# GSM_Power_On-Off_Switch_IC.net
KiCad netlist of a schematic drawn in Altium Designer
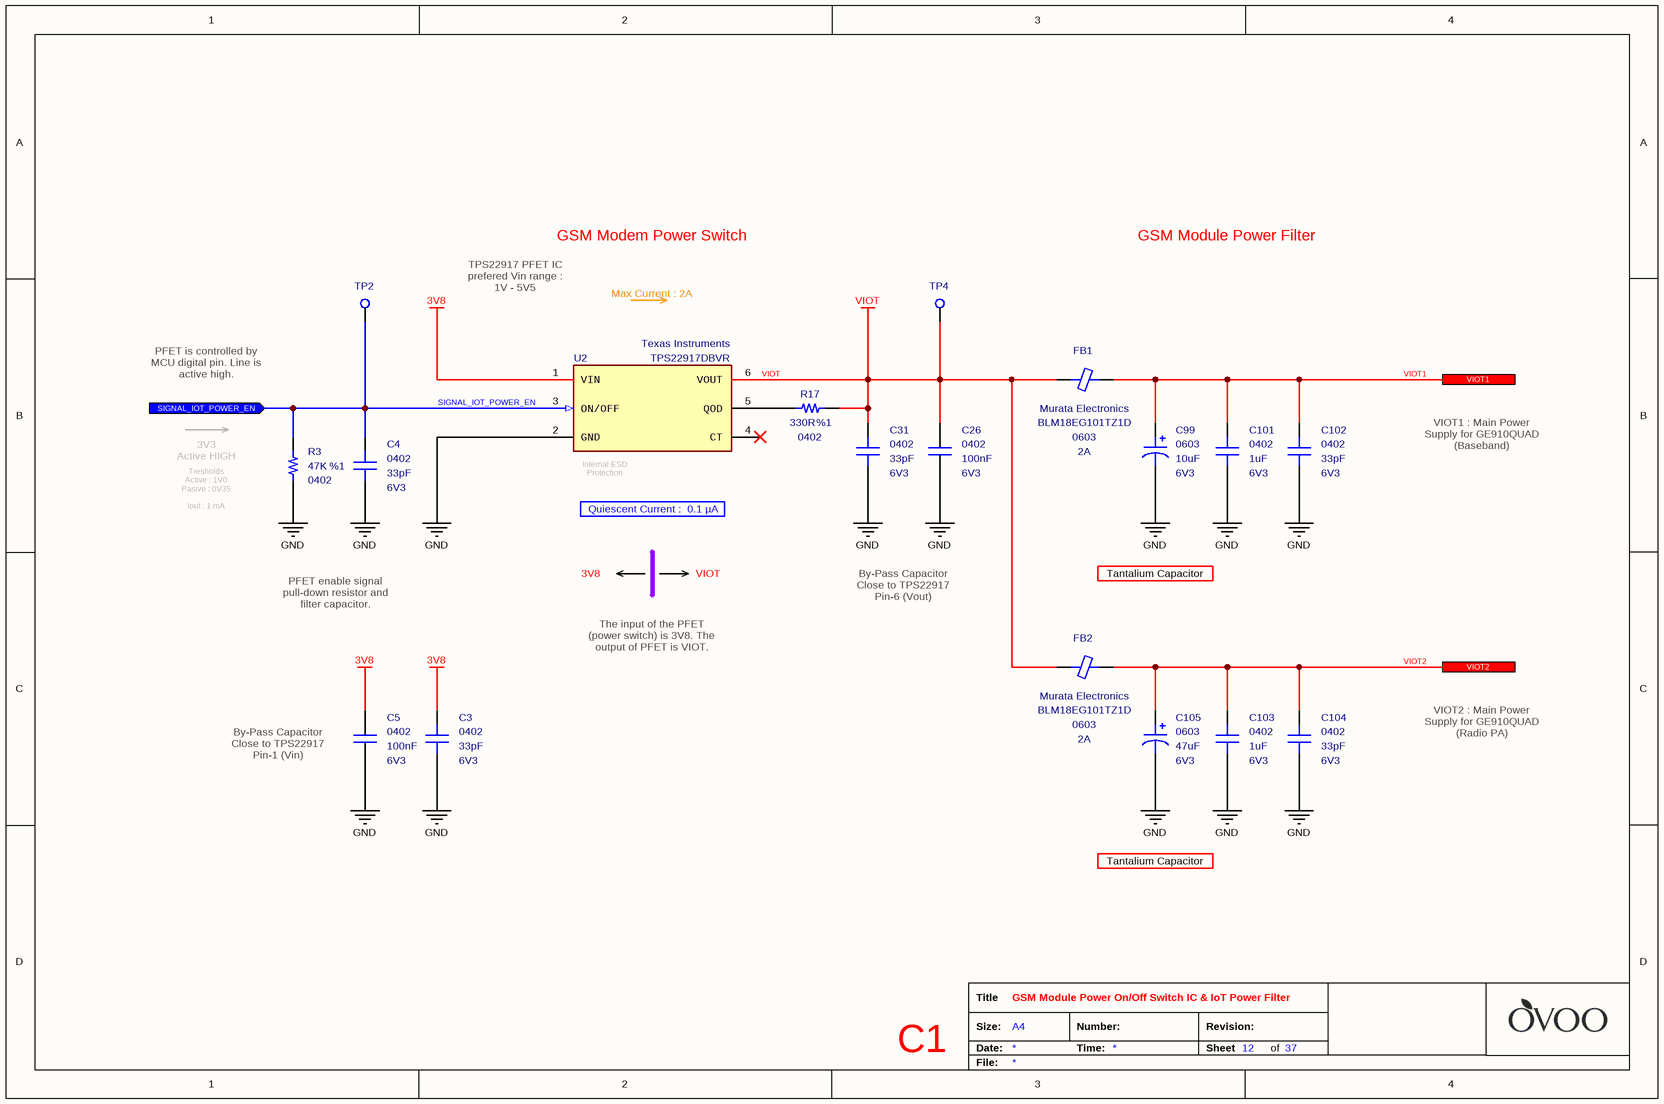
[diagram p0: GSM Power On-Off Switch IC.SchDoc]

(export (version "E")
  (design (tool "Eeschema 10.0.6"))
  (components
    (comp (ref "C3")
      (value "33pF")
      (footprint "CAPACITOR_0402")
      (description "Capacitor - 33pF [0402] (Ceramic)")
      (fields
        (field (name "MANUFACTURER_PART_NUMBER") "C0402C330J9RACAUTO")
        (field (name "MOUSER_PART_NUMBER") "80-C0402C330J9RAUTO")
        (field (name "CASE") "0402")
        (field (name "VOLTAGE") "6V3")
      )
      (libsource (lib "Ovoo_Schematic") (part "Capacitor - 33pF [0402-6V3]"))
    )
    (comp (ref "C4")
      (value "33pF")
      (footprint "CAPACITOR_0402")
      (description "Capacitor - 33pF [0402] (Ceramic)")
      (fields
        (field (name "MANUFACTURER_PART_NUMBER") "C0402C330J9RACAUTO")
        (field (name "MOUSER_PART_NUMBER") "80-C0402C330J9RAUTO")
        (field (name "CASE") "0402")
        (field (name "VOLTAGE") "6V3")
      )
      (libsource (lib "Ovoo_Schematic") (part "Capacitor - 33pF [0402-6V3]"))
    )
    (comp (ref "C5")
      (value "100nF")
      (footprint "CAPACITOR_0402")
      (description "Capacitor - 100nF [0402-6V3] (Ceramic)")
      (fields
        (field (name "MANUFACTURER_PART_NUMBER") "04026D104KAT4A")
        (field (name "MOUSER_PART_NUMBER") "581-04026D104KAT4A")
        (field (name "CASE") "0402")
        (field (name "VOLTAGE") "6V3")
      )
      (libsource (lib "Ovoo_Schematic") (part "Capacitor - 100nF [0402-6V3]"))
    )
    (comp (ref "C26")
      (value "100nF")
      (footprint "CAPACITOR_0402")
      (description "Capacitor - 100nF [0402-6V3] (Ceramic)")
      (fields
        (field (name "MANUFACTURER_PART_NUMBER") "04026D104KAT4A")
        (field (name "MOUSER_PART_NUMBER") "581-04026D104KAT4A")
        (field (name "CASE") "0402")
        (field (name "VOLTAGE") "6V3")
      )
      (libsource (lib "Ovoo_Schematic") (part "Capacitor - 100nF [0402-6V3]"))
    )
    (comp (ref "C31")
      (value "33pF")
      (footprint "CAPACITOR_0402")
      (description "Capacitor - 33pF [0402] (Ceramic)")
      (fields
        (field (name "MANUFACTURER_PART_NUMBER") "C0402C330J9RACAUTO")
        (field (name "MOUSER_PART_NUMBER") "80-C0402C330J9RAUTO")
        (field (name "CASE") "0402")
        (field (name "VOLTAGE") "6V3")
      )
      (libsource (lib "Ovoo_Schematic") (part "Capacitor - 33pF [0402-6V3]"))
    )
    (comp (ref "C99")
      (value "10uF")
      (footprint "CAPACITOR_0603 - TANTALUM")
      (description "Capacitor - 10uF [0603] (Tantalium)")
      (fields
        (field (name "MANUFACTURER_PART_NUMBER") "F380J106MMAAH3")
        (field (name "MOUSER_PART_NUMBER") "581-F380J106MMAAH3")
        (field (name "CASE") "0603")
        (field (name "VOLTAGE") "6V3")
      )
      (libsource (lib "Ovoo_Schematic") (part "Capacitor - 10uF [0603-6V3] (Tantalium)"))
    )
    (comp (ref "C101")
      (value "1uF")
      (footprint "CAPACITOR_0402")
      (description "Capacitor - 1uF [0402] (Ceramic)")
      (fields
        (field (name "MANUFACTURER_PART_NUMBER") "GRM153R60J105ME95D")
        (field (name "MOUSER_PART_NUMBER") "81-GRM153R60J105ME5D")
        (field (name "CASE") "0402")
        (field (name "VOLTAGE") "6V3")
      )
      (libsource (lib "Ovoo_Schematic") (part "Capacitor - 1uF [0402-6V3)"))
    )
    (comp (ref "C102")
      (value "33pF")
      (footprint "CAPACITOR_0402")
      (description "Capacitor - 33pF [0402] (Ceramic)")
      (fields
        (field (name "MANUFACTURER_PART_NUMBER") "C0402C330J9RACAUTO")
        (field (name "MOUSER_PART_NUMBER") "80-C0402C330J9RAUTO")
        (field (name "CASE") "0402")
        (field (name "VOLTAGE") "6V3")
      )
      (libsource (lib "Ovoo_Schematic") (part "Capacitor - 33pF [0402-6V3]"))
    )
    (comp (ref "C103")
      (value "1uF")
      (footprint "CAPACITOR_0402")
      (description "Capacitor - 1uF [0402] (Ceramic)")
      (fields
        (field (name "MANUFACTURER_PART_NUMBER") "GRM153R60J105ME95D")
        (field (name "MOUSER_PART_NUMBER") "81-GRM153R60J105ME5D")
        (field (name "CASE") "0402")
        (field (name "VOLTAGE") "6V3")
      )
      (libsource (lib "Ovoo_Schematic") (part "Capacitor - 1uF [0402-6V3)"))
    )
    (comp (ref "C104")
      (value "33pF")
      (footprint "CAPACITOR_0402")
      (description "Capacitor - 33pF [0402] (Ceramic)")
      (fields
        (field (name "MANUFACTURER_PART_NUMBER") "C0402C330J9RACAUTO")
        (field (name "MOUSER_PART_NUMBER") "80-C0402C330J9RAUTO")
        (field (name "CASE") "0402")
        (field (name "VOLTAGE") "6V3")
      )
      (libsource (lib "Ovoo_Schematic") (part "Capacitor - 33pF [0402-6V3]"))
    )
    (comp (ref "C105")
      (value "47uF")
      (footprint "CAPACITOR_0603 - TANTALUM")
      (description "Capacitor - 47uF [0603] (Tantalium)")
      (fields
        (field (name "MANUFACTURER_PART_NUMBER") "F380J476MMAAXEH3")
        (field (name "MOUSER_PART_NUMBER") "581-F380J476MMAAXEH3")
        (field (name "CASE") "0603")
        (field (name "VOLTAGE") "6V3")
      )
      (libsource (lib "Ovoo_Schematic") (part "Capacitor - 47u [0603-6V3] (Tantalium)"))
    )
    (comp (ref "FB1")
      (value "BLM18EG101TZ1D")
      (footprint "INDUCATOR_0603")
      (description "Ferrite Beads 0603 100ohms 2000mA Auto Infotainment")
      (fields
        (field (name "MOUSER_PART_NUMBER") "81-BLM18EG101TZ1D")
        (field (name "TOLERANCE") "25%")
        (field (name "MANUFACTURER_NAME") "Murata Electronics")
        (field (name "CASE") "0603")
        (field (name "MAXIMUM DC CURRENT") "2A")
      )
      (libsource (lib "Ovoo_Schematic") (part "Ferrite Bead - 2A [0603]"))
    )
    (comp (ref "FB2")
      (value "BLM18EG101TZ1D")
      (footprint "INDUCATOR_0603")
      (description "Ferrite Beads 0603 100ohms 2000mA Auto Infotainment")
      (fields
        (field (name "MOUSER_PART_NUMBER") "81-BLM18EG101TZ1D")
        (field (name "TOLERANCE") "25%")
        (field (name "MANUFACTURER_NAME") "Murata Electronics")
        (field (name "CASE") "0603")
        (field (name "MAXIMUM DC CURRENT") "2A")
      )
      (libsource (lib "Ovoo_Schematic") (part "Ferrite Bead - 2A [0603]"))
    )
    (comp (ref "R3")
      (value "47K")
      (footprint "RESISTOR_0402")
      (description "Thick Film Resistors - SMD 1/16 W 47 Kohms 1%")
      (fields
        (field (name "MANUFACTURER_PART_NUMBER") "CRCW040247K0FKED")
        (field (name "MOUSER_PART_NUMBER") "71-CRCW0402-47K-E3")
        (field (name "TOLERANCE") "%1")
        (field (name "CASE") "0402")
      )
      (libsource (lib "Ovoo_Schematic") (part "Resistor - 47K"))
    )
    (comp (ref "R17")
      (value "330R")
      (footprint "RESISTOR_0402")
      (description "Thick Film Resistors - SMD 1/16 W 330 Ohm 1%")
      (fields
        (field (name "MANUFACTURER_PART_NUMBER") "CRCW0402330RFKED")
        (field (name "MOUSER_PART_NUMBER") "71-CRCW0402-330-E3")
        (field (name "TOLERANCE") "%1")
        (field (name "CASE") "0402")
      )
      (libsource (lib "Ovoo_Schematic") (part "Resistor - 330R"))
    )
    (comp (ref "TP2")
      (value "PCB - Test Point")
      (footprint "Test_Pad - Hole")
      (description "Test Point")
      (libsource (lib "Ovoo_Schematic") (part "PCB - Test Point"))
    )
    (comp (ref "TP4")
      (value "PCB - Test Point")
      (footprint "Test_Pad - Hole")
      (description "Test Point")
      (libsource (lib "Ovoo_Schematic") (part "PCB - Test Point"))
    )
    (comp (ref "U2")
      (value "Power Switch")
      (footprint "SOT-23-6")
      (description "Power Switch MosFet")
      (fields
        (field (name "MOUSER_PART_NUMBER") "595-TPS22917DBVR")
        (field (name "MANUFACTURER_PART_NUMBER") "TPS22917DBVR")
        (field (name "MANUFACTURER_NAME") "Texas Instruments")
      )
      (libsource (lib "Ovoo_Schematic") (part "IC - TPS22917DBVR"))
    )
  )
  (nets
    (net (code "1") (name "/SIGNAL_IOT_POWER_EN") (class "Default")
      (node (ref "C4") (pin "2") (pinfunction "2_2") (pintype "passive"))
      (node (ref "R3") (pin "2") (pinfunction "2_2") (pintype "passive"))
      (node (ref "TP2") (pin "1") (pinfunction "1_1") (pintype "passive"))
      (node (ref "U2") (pin "3") (pinfunction "ON/OFF_3") (pintype "input"))
    )
    (net (code "2") (name "/VIOT1") (class "Default")
      (node (ref "C101") (pin "2") (pinfunction "2_2") (pintype "passive"))
      (node (ref "C102") (pin "2") (pinfunction "2_2") (pintype "passive"))
      (node (ref "C99") (pin "1") (pinfunction "1_1") (pintype "passive"))
      (node (ref "FB1") (pin "2") (pinfunction "2_2") (pintype "passive"))
    )
    (net (code "3") (name "/VIOT2") (class "Default")
      (node (ref "C103") (pin "2") (pinfunction "2_2") (pintype "passive"))
      (node (ref "C104") (pin "2") (pinfunction "2_2") (pintype "passive"))
      (node (ref "C105") (pin "1") (pinfunction "1_1") (pintype "passive"))
      (node (ref "FB2") (pin "2") (pinfunction "2_2") (pintype "passive"))
    )
    (net (code "4") (name "3V8") (class "Default")
      (node (ref "C3") (pin "2") (pinfunction "2_2") (pintype "passive"))
      (node (ref "C5") (pin "1") (pinfunction "1_1") (pintype "passive"))
      (node (ref "U2") (pin "1") (pinfunction "VIN_1") (pintype "power_in"))
    )
    (net (code "5") (name "GND") (class "Default")
      (node (ref "C101") (pin "1") (pinfunction "1_1") (pintype "passive"))
      (node (ref "C102") (pin "1") (pinfunction "1_1") (pintype "passive"))
      (node (ref "C103") (pin "1") (pinfunction "1_1") (pintype "passive"))
      (node (ref "C104") (pin "1") (pinfunction "1_1") (pintype "passive"))
      (node (ref "C105") (pin "2") (pinfunction "2_2") (pintype "passive"))
      (node (ref "C26") (pin "2") (pinfunction "2_2") (pintype "passive"))
      (node (ref "C3") (pin "1") (pinfunction "1_1") (pintype "passive"))
      (node (ref "C31") (pin "1") (pinfunction "1_1") (pintype "passive"))
      (node (ref "C4") (pin "1") (pinfunction "1_1") (pintype "passive"))
      (node (ref "C5") (pin "2") (pinfunction "2_2") (pintype "passive"))
      (node (ref "C99") (pin "2") (pinfunction "2_2") (pintype "passive"))
      (node (ref "R3") (pin "1") (pinfunction "1_1") (pintype "passive"))
      (node (ref "U2") (pin "2") (pinfunction "GND_2") (pintype "power_in"))
    )
    (net (code "6") (name "Net-(U2-QOD)") (class "Default")
      (node (ref "R17") (pin "2") (pinfunction "2_2") (pintype "passive"))
      (node (ref "U2") (pin "5") (pinfunction "QOD_5") (pintype "power_in"))
    )
    (net (code "7") (name "VIOT") (class "Default")
      (node (ref "C26") (pin "1") (pinfunction "1_1") (pintype "passive"))
      (node (ref "C31") (pin "2") (pinfunction "2_2") (pintype "passive"))
      (node (ref "FB1") (pin "1") (pinfunction "1_1") (pintype "passive"))
      (node (ref "FB2") (pin "1") (pinfunction "1_1") (pintype "passive"))
      (node (ref "R17") (pin "1") (pinfunction "1_1") (pintype "passive"))
      (node (ref "TP4") (pin "1") (pinfunction "1_1") (pintype "passive"))
      (node (ref "U2") (pin "6") (pinfunction "VOUT_6") (pintype "power_in"))
    )
    (net (code "8") (name "unconnected-(U2-CT-Pad4)") (class "Default")
      (node (ref "U2") (pin "4") (pinfunction "CT_4") (pintype "power_in+no_connect"))
    )
  )
)
